# BlinkyTile.net
KiCad netlist of a schematic drawn in EAGLE
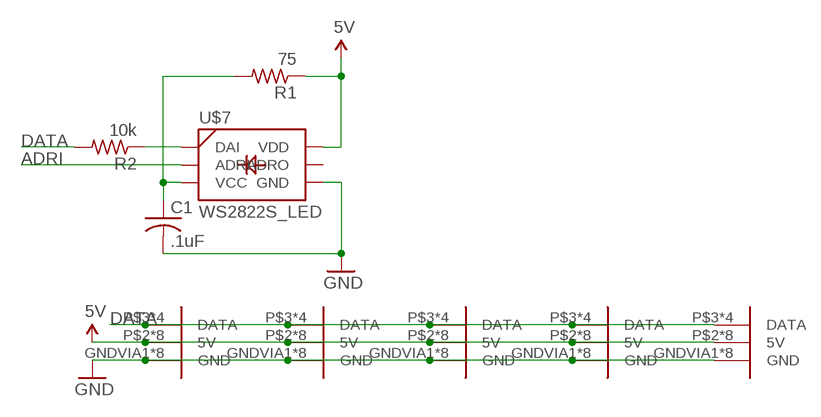
[diagram p0: schematic, sheet 1]

(export (version "E")
  (design (tool "Eeschema 10.0.6"))
  (components
    (comp (ref "C1")
      (value ".1uF")
      (footprint "eagle-import:C0603")
      (libsource (lib "eagle-import") (part "C-USC0603"))
    )
    (comp (ref "R1")
      (value "75")
      (footprint "eagle-import:R0603")
      (libsource (lib "eagle-import") (part "R-US_R0603"))
    )
    (comp (ref "R2")
      (value "10k")
      (footprint "eagle-import:R0603")
      (libsource (lib "eagle-import") (part "R-US_R0603"))
    )
    (comp (ref "U$2")
      (value "D_EDGEMOD")
      (footprint "eagle-import:D_EDGE_SLOT_MOD")
      (libsource (lib "eagle-import") (part "D_EDGEMOD"))
    )
    (comp (ref "U$3")
      (value "D_EDGEMOD")
      (footprint "eagle-import:D_EDGE_SLOT_MOD")
      (libsource (lib "eagle-import") (part "D_EDGEMOD"))
    )
    (comp (ref "U$4")
      (value "D_EDGEMOD")
      (footprint "eagle-import:D_EDGE_SLOT_MOD")
      (libsource (lib "eagle-import") (part "D_EDGEMOD"))
    )
    (comp (ref "U$5")
      (value "D_EDGEMOD")
      (footprint "eagle-import:D_EDGE_SLOT_MOD")
      (libsource (lib "eagle-import") (part "D_EDGEMOD"))
    )
    (comp (ref "U$6")
      (value "D_EDGEMOD")
      (footprint "eagle-import:D_EDGE_SLOT_MOD")
      (libsource (lib "eagle-import") (part "D_EDGEMOD"))
    )
    (comp (ref "U$7")
      (value "WS2822S_LED")
      (footprint "eagle-import:WS2822S_LED")
      (libsource (lib "eagle-import") (part "WS2822S_LED"))
    )
  )
  (nets
    (net (code "1") (name "/ADRI") (class "Default")
      (node (ref "U$7") (pin "2") (pinfunction "ADRI_2") (pintype "input"))
    )
    (net (code "2") (name "/DATA") (class "Default")
      (node (ref "R2") (pin "2") (pinfunction "2_2") (pintype "passive"))
      (node (ref "U$2") (pin "P$3") (pinfunction "DATA_P$3") (pintype "bidirectional"))
      (node (ref "U$2") (pin "P$8") (pinfunction "DATA_P$8") (pintype "bidirectional"))
      (node (ref "U$2") (pin "SIGVIA1") (pinfunction "DATA_SIGVIA1") (pintype "bidirectional"))
      (node (ref "U$2") (pin "SIGVIA3") (pinfunction "DATA_SIGVIA3") (pintype "bidirectional"))
      (node (ref "U$3") (pin "P$3") (pinfunction "DATA_P$3") (pintype "bidirectional"))
      (node (ref "U$3") (pin "P$8") (pinfunction "DATA_P$8") (pintype "bidirectional"))
      (node (ref "U$3") (pin "SIGVIA1") (pinfunction "DATA_SIGVIA1") (pintype "bidirectional"))
      (node (ref "U$3") (pin "SIGVIA3") (pinfunction "DATA_SIGVIA3") (pintype "bidirectional"))
      (node (ref "U$4") (pin "P$3") (pinfunction "DATA_P$3") (pintype "bidirectional"))
      (node (ref "U$4") (pin "P$8") (pinfunction "DATA_P$8") (pintype "bidirectional"))
      (node (ref "U$4") (pin "SIGVIA1") (pinfunction "DATA_SIGVIA1") (pintype "bidirectional"))
      (node (ref "U$4") (pin "SIGVIA3") (pinfunction "DATA_SIGVIA3") (pintype "bidirectional"))
      (node (ref "U$5") (pin "P$3") (pinfunction "DATA_P$3") (pintype "bidirectional"))
      (node (ref "U$5") (pin "P$8") (pinfunction "DATA_P$8") (pintype "bidirectional"))
      (node (ref "U$5") (pin "SIGVIA1") (pinfunction "DATA_SIGVIA1") (pintype "bidirectional"))
      (node (ref "U$5") (pin "SIGVIA3") (pinfunction "DATA_SIGVIA3") (pintype "bidirectional"))
      (node (ref "U$6") (pin "P$3") (pinfunction "DATA_P$3") (pintype "bidirectional"))
      (node (ref "U$6") (pin "P$8") (pinfunction "DATA_P$8") (pintype "bidirectional"))
      (node (ref "U$6") (pin "SIGVIA1") (pinfunction "DATA_SIGVIA1") (pintype "bidirectional"))
      (node (ref "U$6") (pin "SIGVIA3") (pinfunction "DATA_SIGVIA3") (pintype "bidirectional"))
    )
    (net (code "3") (name "5V") (class "Default")
      (node (ref "R1") (pin "1") (pinfunction "1_1") (pintype "passive"))
      (node (ref "U$2") (pin "P$2") (pinfunction "5V_P$2") (pintype "bidirectional"))
      (node (ref "U$2") (pin "P$4") (pinfunction "5V_P$4") (pintype "bidirectional"))
      (node (ref "U$2") (pin "P$7") (pinfunction "5V_P$7") (pintype "bidirectional"))
      (node (ref "U$2") (pin "P$9") (pinfunction "5V_P$9") (pintype "bidirectional"))
      (node (ref "U$2") (pin "PWRVIA1") (pinfunction "5V_PWRVIA1") (pintype "bidirectional"))
      (node (ref "U$2") (pin "PWRVIA3") (pinfunction "5V_PWRVIA3") (pintype "bidirectional"))
      (node (ref "U$2") (pin "PWRVIA4") (pinfunction "5V_PWRVIA4") (pintype "bidirectional"))
      (node (ref "U$2") (pin "PWRVIA6") (pinfunction "5V_PWRVIA6") (pintype "bidirectional"))
      (node (ref "U$3") (pin "P$2") (pinfunction "5V_P$2") (pintype "bidirectional"))
      (node (ref "U$3") (pin "P$4") (pinfunction "5V_P$4") (pintype "bidirectional"))
      (node (ref "U$3") (pin "P$7") (pinfunction "5V_P$7") (pintype "bidirectional"))
      (node (ref "U$3") (pin "P$9") (pinfunction "5V_P$9") (pintype "bidirectional"))
      (node (ref "U$3") (pin "PWRVIA1") (pinfunction "5V_PWRVIA1") (pintype "bidirectional"))
      (node (ref "U$3") (pin "PWRVIA3") (pinfunction "5V_PWRVIA3") (pintype "bidirectional"))
      (node (ref "U$3") (pin "PWRVIA4") (pinfunction "5V_PWRVIA4") (pintype "bidirectional"))
      (node (ref "U$3") (pin "PWRVIA6") (pinfunction "5V_PWRVIA6") (pintype "bidirectional"))
      (node (ref "U$4") (pin "P$2") (pinfunction "5V_P$2") (pintype "bidirectional"))
      (node (ref "U$4") (pin "P$4") (pinfunction "5V_P$4") (pintype "bidirectional"))
      (node (ref "U$4") (pin "P$7") (pinfunction "5V_P$7") (pintype "bidirectional"))
      (node (ref "U$4") (pin "P$9") (pinfunction "5V_P$9") (pintype "bidirectional"))
      (node (ref "U$4") (pin "PWRVIA1") (pinfunction "5V_PWRVIA1") (pintype "bidirectional"))
      (node (ref "U$4") (pin "PWRVIA3") (pinfunction "5V_PWRVIA3") (pintype "bidirectional"))
      (node (ref "U$4") (pin "PWRVIA4") (pinfunction "5V_PWRVIA4") (pintype "bidirectional"))
      (node (ref "U$4") (pin "PWRVIA6") (pinfunction "5V_PWRVIA6") (pintype "bidirectional"))
      (node (ref "U$5") (pin "P$2") (pinfunction "5V_P$2") (pintype "bidirectional"))
      (node (ref "U$5") (pin "P$4") (pinfunction "5V_P$4") (pintype "bidirectional"))
      (node (ref "U$5") (pin "P$7") (pinfunction "5V_P$7") (pintype "bidirectional"))
      (node (ref "U$5") (pin "P$9") (pinfunction "5V_P$9") (pintype "bidirectional"))
      (node (ref "U$5") (pin "PWRVIA1") (pinfunction "5V_PWRVIA1") (pintype "bidirectional"))
      (node (ref "U$5") (pin "PWRVIA3") (pinfunction "5V_PWRVIA3") (pintype "bidirectional"))
      (node (ref "U$5") (pin "PWRVIA4") (pinfunction "5V_PWRVIA4") (pintype "bidirectional"))
      (node (ref "U$5") (pin "PWRVIA6") (pinfunction "5V_PWRVIA6") (pintype "bidirectional"))
      (node (ref "U$6") (pin "P$2") (pinfunction "5V_P$2") (pintype "bidirectional"))
      (node (ref "U$6") (pin "P$4") (pinfunction "5V_P$4") (pintype "bidirectional"))
      (node (ref "U$6") (pin "P$7") (pinfunction "5V_P$7") (pintype "bidirectional"))
      (node (ref "U$6") (pin "P$9") (pinfunction "5V_P$9") (pintype "bidirectional"))
      (node (ref "U$6") (pin "PWRVIA1") (pinfunction "5V_PWRVIA1") (pintype "bidirectional"))
      (node (ref "U$6") (pin "PWRVIA3") (pinfunction "5V_PWRVIA3") (pintype "bidirectional"))
      (node (ref "U$6") (pin "PWRVIA4") (pinfunction "5V_PWRVIA4") (pintype "bidirectional"))
      (node (ref "U$6") (pin "PWRVIA6") (pinfunction "5V_PWRVIA6") (pintype "bidirectional"))
      (node (ref "U$7") (pin "6") (pinfunction "VDD_6") (pintype "power_in"))
    )
    (net (code "4") (name "GND") (class "Default")
      (node (ref "C1") (pin "2") (pinfunction "2_2") (pintype "passive"))
      (node (ref "U$2") (pin "GNDVIA1") (pinfunction "GND_GNDVIA1") (pintype "bidirectional"))
      (node (ref "U$2") (pin "GNDVIA3") (pinfunction "GND_GNDVIA3") (pintype "bidirectional"))
      (node (ref "U$2") (pin "GNDVIA4") (pinfunction "GND_GNDVIA4") (pintype "bidirectional"))
      (node (ref "U$2") (pin "GNDVIA6") (pinfunction "GND_GNDVIA6") (pintype "bidirectional"))
      (node (ref "U$2") (pin "P$1") (pinfunction "GND_P$1") (pintype "bidirectional"))
      (node (ref "U$2") (pin "P$10") (pinfunction "GND_P$10") (pintype "bidirectional"))
      (node (ref "U$2") (pin "P$5") (pinfunction "GND_P$5") (pintype "bidirectional"))
      (node (ref "U$2") (pin "P$6") (pinfunction "GND_P$6") (pintype "bidirectional"))
      (node (ref "U$3") (pin "GNDVIA1") (pinfunction "GND_GNDVIA1") (pintype "bidirectional"))
      (node (ref "U$3") (pin "GNDVIA3") (pinfunction "GND_GNDVIA3") (pintype "bidirectional"))
      (node (ref "U$3") (pin "GNDVIA4") (pinfunction "GND_GNDVIA4") (pintype "bidirectional"))
      (node (ref "U$3") (pin "GNDVIA6") (pinfunction "GND_GNDVIA6") (pintype "bidirectional"))
      (node (ref "U$3") (pin "P$1") (pinfunction "GND_P$1") (pintype "bidirectional"))
      (node (ref "U$3") (pin "P$10") (pinfunction "GND_P$10") (pintype "bidirectional"))
      (node (ref "U$3") (pin "P$5") (pinfunction "GND_P$5") (pintype "bidirectional"))
      (node (ref "U$3") (pin "P$6") (pinfunction "GND_P$6") (pintype "bidirectional"))
      (node (ref "U$4") (pin "GNDVIA1") (pinfunction "GND_GNDVIA1") (pintype "bidirectional"))
      (node (ref "U$4") (pin "GNDVIA3") (pinfunction "GND_GNDVIA3") (pintype "bidirectional"))
      (node (ref "U$4") (pin "GNDVIA4") (pinfunction "GND_GNDVIA4") (pintype "bidirectional"))
      (node (ref "U$4") (pin "GNDVIA6") (pinfunction "GND_GNDVIA6") (pintype "bidirectional"))
      (node (ref "U$4") (pin "P$1") (pinfunction "GND_P$1") (pintype "bidirectional"))
      (node (ref "U$4") (pin "P$10") (pinfunction "GND_P$10") (pintype "bidirectional"))
      (node (ref "U$4") (pin "P$5") (pinfunction "GND_P$5") (pintype "bidirectional"))
      (node (ref "U$4") (pin "P$6") (pinfunction "GND_P$6") (pintype "bidirectional"))
      (node (ref "U$5") (pin "GNDVIA1") (pinfunction "GND_GNDVIA1") (pintype "bidirectional"))
      (node (ref "U$5") (pin "GNDVIA3") (pinfunction "GND_GNDVIA3") (pintype "bidirectional"))
      (node (ref "U$5") (pin "GNDVIA4") (pinfunction "GND_GNDVIA4") (pintype "bidirectional"))
      (node (ref "U$5") (pin "GNDVIA6") (pinfunction "GND_GNDVIA6") (pintype "bidirectional"))
      (node (ref "U$5") (pin "P$1") (pinfunction "GND_P$1") (pintype "bidirectional"))
      (node (ref "U$5") (pin "P$10") (pinfunction "GND_P$10") (pintype "bidirectional"))
      (node (ref "U$5") (pin "P$5") (pinfunction "GND_P$5") (pintype "bidirectional"))
      (node (ref "U$5") (pin "P$6") (pinfunction "GND_P$6") (pintype "bidirectional"))
      (node (ref "U$6") (pin "GNDVIA1") (pinfunction "GND_GNDVIA1") (pintype "bidirectional"))
      (node (ref "U$6") (pin "GNDVIA3") (pinfunction "GND_GNDVIA3") (pintype "bidirectional"))
      (node (ref "U$6") (pin "GNDVIA4") (pinfunction "GND_GNDVIA4") (pintype "bidirectional"))
      (node (ref "U$6") (pin "GNDVIA6") (pinfunction "GND_GNDVIA6") (pintype "bidirectional"))
      (node (ref "U$6") (pin "P$1") (pinfunction "GND_P$1") (pintype "bidirectional"))
      (node (ref "U$6") (pin "P$10") (pinfunction "GND_P$10") (pintype "bidirectional"))
      (node (ref "U$6") (pin "P$5") (pinfunction "GND_P$5") (pintype "bidirectional"))
      (node (ref "U$6") (pin "P$6") (pinfunction "GND_P$6") (pintype "bidirectional"))
      (node (ref "U$7") (pin "4") (pinfunction "GND_4") (pintype "power_in"))
    )
    (net (code "5") (name "Net-(U$7-DAI)") (class "Default")
      (node (ref "R2") (pin "1") (pinfunction "1_1") (pintype "passive"))
      (node (ref "U$7") (pin "1") (pinfunction "DAI_1") (pintype "input"))
    )
    (net (code "6") (name "Net-(U$7-VCC)") (class "Default")
      (node (ref "C1") (pin "1") (pinfunction "1_1") (pintype "passive"))
      (node (ref "R1") (pin "2") (pinfunction "2_2") (pintype "passive"))
      (node (ref "U$7") (pin "3") (pinfunction "VCC_3") (pintype "power_in"))
    )
    (net (code "7") (name "unconnected-(U$7-ADRO-Pad5)") (class "Default")
      (node (ref "U$7") (pin "5") (pinfunction "ADRO_5") (pintype "output"))
    )
  )
)
